# Badge_Schematic.net
KiCad netlist of a schematic drawn in EAGLE
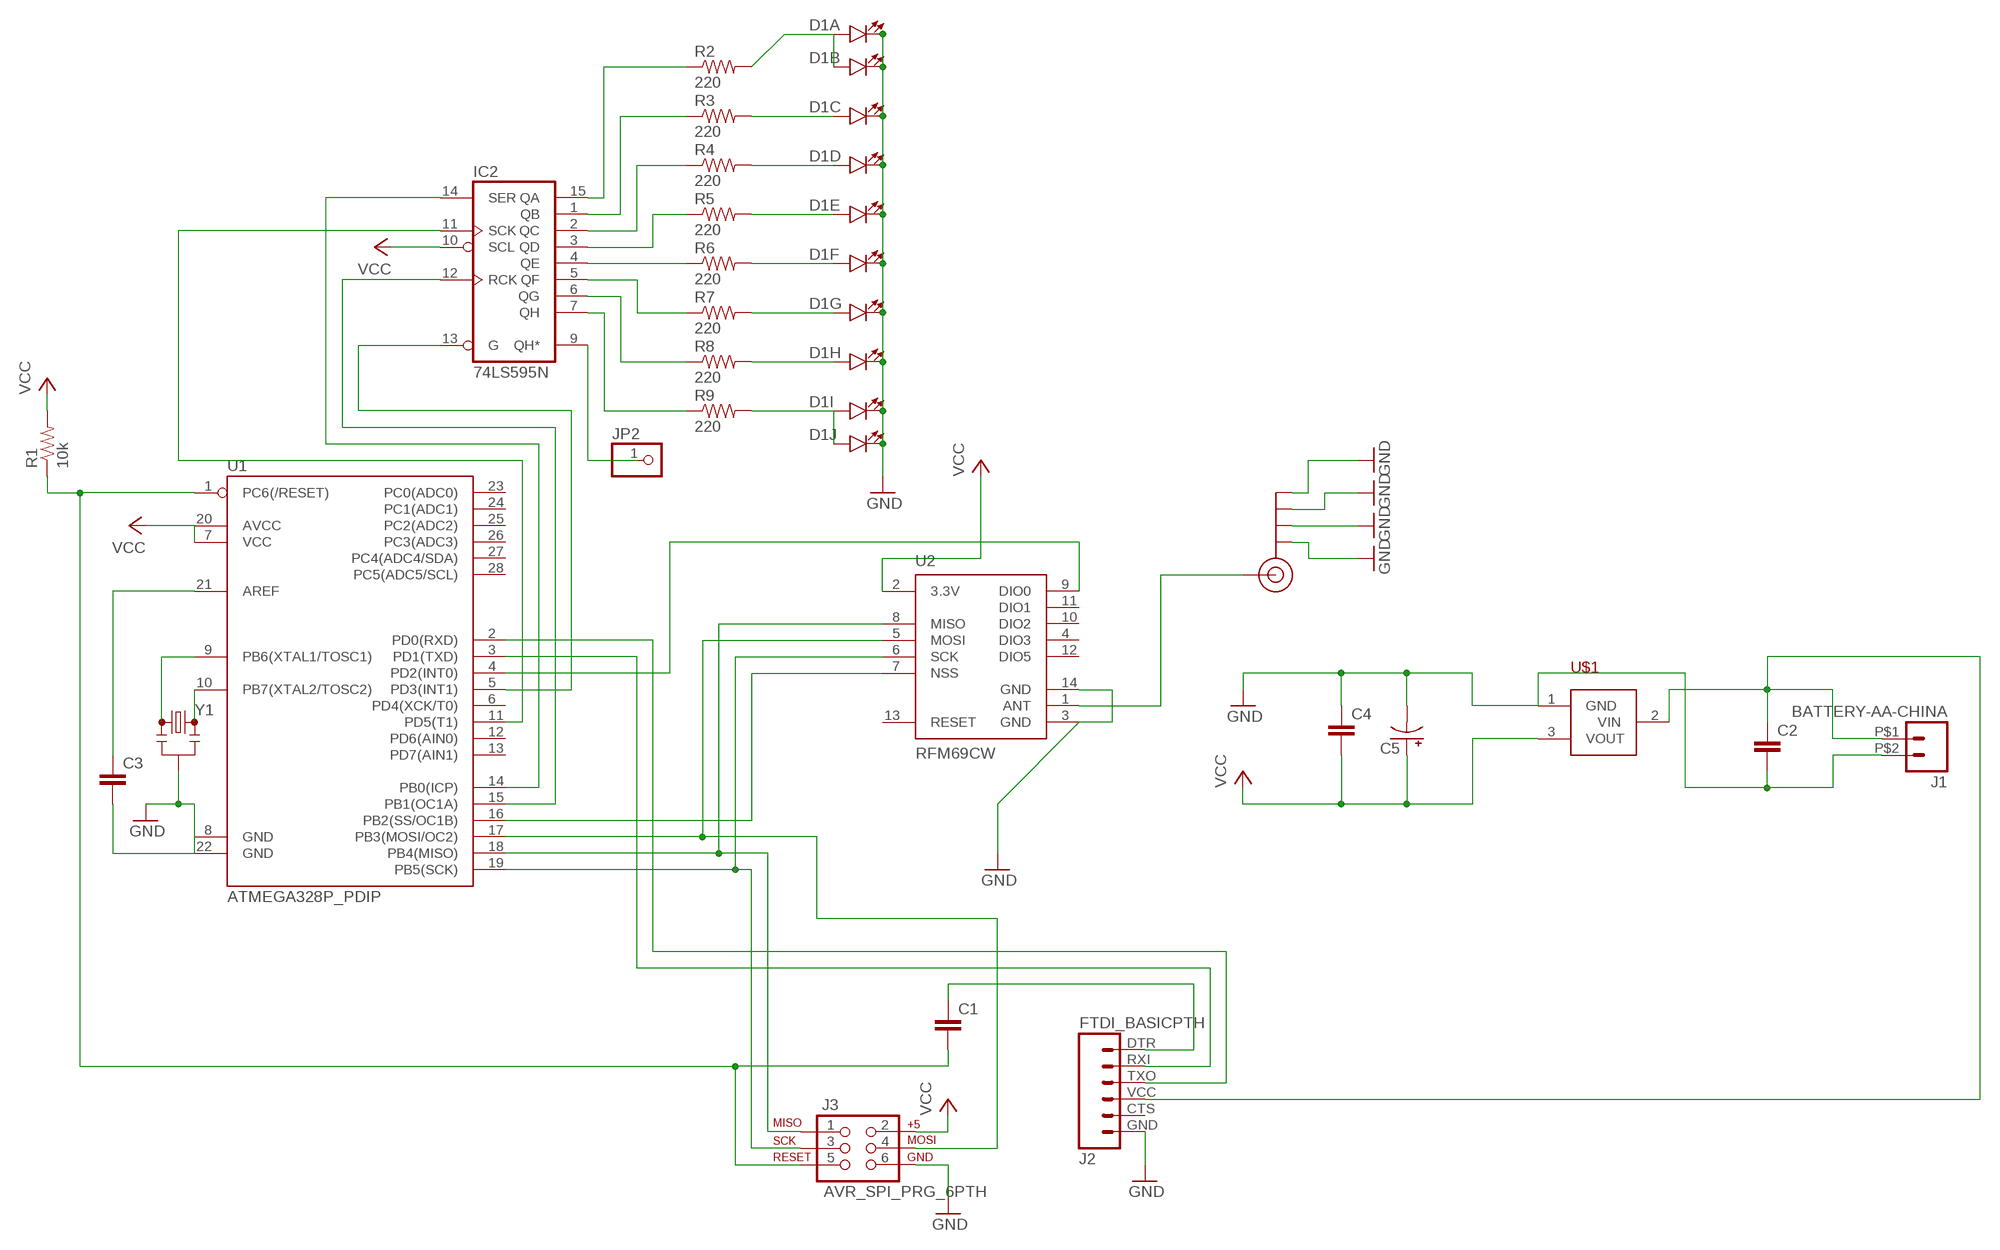
[diagram p0: schematic, sheet 1]

(export (version "E")
  (design (tool "Eeschema 10.0.6"))
  (components
    (comp (ref "C1")
      (value "0.1UF-50V-20%(PTH)KIT-EZ")
      (footprint "eagle-import:CAP-PTH-SMALL-KIT")
      (libsource (lib "eagle-import") (part "0.1UF-50V-20%(PTH)KIT-EZ"))
    )
    (comp (ref "C2")
      (value "0.1UF-50V-20%(PTH)KIT-EZ")
      (footprint "eagle-import:CAP-PTH-SMALL-KIT")
      (libsource (lib "eagle-import") (part "0.1UF-50V-20%(PTH)KIT-EZ"))
    )
    (comp (ref "C3")
      (value "0.1UF-50V-20%(PTH)KIT-EZ")
      (footprint "eagle-import:CAP-PTH-SMALL-KIT")
      (libsource (lib "eagle-import") (part "0.1UF-50V-20%(PTH)KIT-EZ"))
    )
    (comp (ref "C4")
      (value "0.1UF-50V-20%(PTH)KIT-EZ")
      (footprint "eagle-import:CAP-PTH-SMALL-KIT")
      (libsource (lib "eagle-import") (part "0.1UF-50V-20%(PTH)KIT-EZ"))
    )
    (comp (ref "C5")
      (value "10UF-25V-20%(PTH)KIT")
      (footprint "eagle-import:CPOL-RADIAL-10UF-25V-KIT")
      (libsource (lib "eagle-import") (part "10UF-25V-20%(PTH)KIT"))
    )
    (comp (ref "D1")
      (value "LED_BARGRAPH_10")
      (footprint "eagle-import:LED_BARGAPH_10")
      (libsource (lib "eagle-import") (part "LED_BARGRAPH_10"))
    )
    (comp (ref "IC2")
      (value "74LS595N")
      (footprint "eagle-import:DIL16")
      (libsource (lib "eagle-import") (part "74595NLS"))
    )
    (comp (ref "J$1")
      (value "SMA_EDGE")
      (footprint "eagle-import:SMA-EDGE")
      (libsource (lib "eagle-import") (part "SMA_EDGE"))
    )
    (comp (ref "J1")
      (value "BATTERY-AA-CHINA")
      (footprint "eagle-import:BATTERY-AA-CHINA-PACKAGE")
      (libsource (lib "eagle-import") (part "BATTERY-AA-CHINA"))
    )
    (comp (ref "J2")
      (value "FTDI_BASICPTH")
      (footprint "eagle-import:FTDI_BASIC")
      (libsource (lib "eagle-import") (part "FTDI_BASICPTH"))
    )
    (comp (ref "J3")
      (value "AVR_SPI_PRG_6PTH")
      (footprint "eagle-import:2X3")
      (libsource (lib "eagle-import") (part "AVR_SPI_PRG_6PTH"))
    )
    (comp (ref "JP2")
      (value "PINHD-1X1")
      (footprint "eagle-import:1X01")
      (libsource (lib "eagle-import") (part "PINHD-1X1"))
    )
    (comp (ref "R1")
      (value "10k")
      (footprint "eagle-import:AXIAL-0.3")
      (libsource (lib "eagle-import") (part "RESISTORAXIAL-0.3"))
    )
    (comp (ref "R2")
      (value "220")
      (footprint "eagle-import:AXIAL-0.3EZ")
      (libsource (lib "eagle-import") (part "RESISTOREZ"))
    )
    (comp (ref "R3")
      (value "220")
      (footprint "eagle-import:AXIAL-0.3EZ")
      (libsource (lib "eagle-import") (part "RESISTOREZ"))
    )
    (comp (ref "R4")
      (value "220")
      (footprint "eagle-import:AXIAL-0.3EZ")
      (libsource (lib "eagle-import") (part "RESISTOREZ"))
    )
    (comp (ref "R5")
      (value "220")
      (footprint "eagle-import:AXIAL-0.3EZ")
      (libsource (lib "eagle-import") (part "RESISTOREZ"))
    )
    (comp (ref "R6")
      (value "220")
      (footprint "eagle-import:AXIAL-0.3EZ")
      (libsource (lib "eagle-import") (part "RESISTOREZ"))
    )
    (comp (ref "R7")
      (value "220")
      (footprint "eagle-import:AXIAL-0.3EZ")
      (libsource (lib "eagle-import") (part "RESISTOREZ"))
    )
    (comp (ref "R8")
      (value "220")
      (footprint "eagle-import:AXIAL-0.3EZ")
      (libsource (lib "eagle-import") (part "RESISTOREZ"))
    )
    (comp (ref "R9")
      (value "220")
      (footprint "eagle-import:AXIAL-0.3EZ")
      (libsource (lib "eagle-import") (part "RESISTOREZ"))
    )
    (comp (ref "U$1")
      (value "MCP1702-33TO92")
      (footprint "eagle-import:TO-92")
      (libsource (lib "eagle-import") (part "MCP1702-33TO92"))
    )
    (comp (ref "U1")
      (value "ATMEGA328P_PDIP")
      (footprint "eagle-import:DIL28-3")
      (libsource (lib "eagle-import") (part "ATMEGA328P_PDIP"))
    )
    (comp (ref "U2")
      (value "RFM69CW")
      (footprint "eagle-import:RFM69CW-XXXS2")
      (libsource (lib "eagle-import") (part "RFM69CW"))
    )
    (comp (ref "Y1")
      (value "RESONATORPTH")
      (footprint "eagle-import:RESONATOR-PTH")
      (libsource (lib "eagle-import") (part "RESONATORPTH"))
    )
  )
  (nets
    (net (code "1") (name "GND") (class "Default")
      (node (ref "C2") (pin "2") (pinfunction "2_2") (pintype "passive"))
      (node (ref "C3") (pin "2") (pinfunction "2_2") (pintype "passive"))
      (node (ref "C4") (pin "1") (pinfunction "1_1") (pintype "passive"))
      (node (ref "C5") (pin "2") (pinfunction "-_2") (pintype "passive"))
      (node (ref "D1") (pin "11") (pinfunction "C_11") (pintype "passive"))
      (node (ref "D1") (pin "12") (pinfunction "C_12") (pintype "passive"))
      (node (ref "D1") (pin "13") (pinfunction "C_13") (pintype "passive"))
      (node (ref "D1") (pin "14") (pinfunction "C_14") (pintype "passive"))
      (node (ref "D1") (pin "15") (pinfunction "C_15") (pintype "passive"))
      (node (ref "D1") (pin "16") (pinfunction "C_16") (pintype "passive"))
      (node (ref "D1") (pin "17") (pinfunction "C_17") (pintype "passive"))
      (node (ref "D1") (pin "18") (pinfunction "C_18") (pintype "passive"))
      (node (ref "D1") (pin "19") (pinfunction "C_19") (pintype "passive"))
      (node (ref "D1") (pin "20") (pinfunction "C_20") (pintype "passive"))
      (node (ref "J$1") (pin "GND@0") (pinfunction "GND_GND@0") (pintype "bidirectional"))
      (node (ref "J$1") (pin "GND@1") (pinfunction "GND_GND@1") (pintype "bidirectional"))
      (node (ref "J$1") (pin "GND@2") (pinfunction "GND_GND@2") (pintype "bidirectional"))
      (node (ref "J$1") (pin "GND@3") (pinfunction "GND_GND@3") (pintype "bidirectional"))
      (node (ref "J1") (pin "P$2") (pinfunction "2_P$2") (pintype "passive"))
      (node (ref "J2") (pin "GND") (pinfunction "6_GND") (pintype "passive"))
      (node (ref "J3") (pin "6") (pinfunction "6_6") (pintype "passive"))
      (node (ref "U$1") (pin "1") (pinfunction "GND_1") (pintype "power_in"))
      (node (ref "U1") (pin "22") (pinfunction "GND_22") (pintype "bidirectional"))
      (node (ref "U1") (pin "8") (pinfunction "GND_8") (pintype "bidirectional"))
      (node (ref "U2") (pin "14") (pinfunction "GND_14") (pintype "power_in"))
      (node (ref "U2") (pin "3") (pinfunction "GND_3") (pintype "power_in"))
      (node (ref "Y1") (pin "2") (pinfunction "2_2") (pintype "passive"))
    )
    (net (code "2") (name "Net-(D1A-A)") (class "Default")
      (node (ref "D1") (pin "1") (pinfunction "A_1") (pintype "passive"))
      (node (ref "D1") (pin "2") (pinfunction "A_2") (pintype "passive"))
      (node (ref "R2") (pin "P$2") (pinfunction "2_P$2") (pintype "passive"))
    )
    (net (code "3") (name "Net-(D1C-A)") (class "Default")
      (node (ref "D1") (pin "3") (pinfunction "A_3") (pintype "passive"))
      (node (ref "R3") (pin "P$2") (pinfunction "2_P$2") (pintype "passive"))
    )
    (net (code "4") (name "Net-(D1D-A)") (class "Default")
      (node (ref "D1") (pin "4") (pinfunction "A_4") (pintype "passive"))
      (node (ref "R4") (pin "P$2") (pinfunction "2_P$2") (pintype "passive"))
    )
    (net (code "5") (name "Net-(D1E-A)") (class "Default")
      (node (ref "D1") (pin "5") (pinfunction "A_5") (pintype "passive"))
      (node (ref "R5") (pin "P$2") (pinfunction "2_P$2") (pintype "passive"))
    )
    (net (code "6") (name "Net-(D1F-A)") (class "Default")
      (node (ref "D1") (pin "6") (pinfunction "A_6") (pintype "passive"))
      (node (ref "R6") (pin "P$2") (pinfunction "2_P$2") (pintype "passive"))
    )
    (net (code "7") (name "Net-(D1G-A)") (class "Default")
      (node (ref "D1") (pin "7") (pinfunction "A_7") (pintype "passive"))
      (node (ref "R7") (pin "P$2") (pinfunction "2_P$2") (pintype "passive"))
    )
    (net (code "8") (name "Net-(D1H-A)") (class "Default")
      (node (ref "D1") (pin "8") (pinfunction "A_8") (pintype "passive"))
      (node (ref "R8") (pin "P$2") (pinfunction "2_P$2") (pintype "passive"))
    )
    (net (code "9") (name "Net-(D1I-A)") (class "Default")
      (node (ref "D1") (pin "10") (pinfunction "A_10") (pintype "passive"))
      (node (ref "D1") (pin "9") (pinfunction "A_9") (pintype "passive"))
      (node (ref "R9") (pin "P$2") (pinfunction "2_P$2") (pintype "passive"))
    )
    (net (code "10") (name "Net-(IC2A-G)") (class "Default")
      (node (ref "IC2") (pin "13") (pinfunction "G_13") (pintype "input"))
      (node (ref "U1") (pin "5") (pinfunction "PD3(INT1)_5") (pintype "bidirectional"))
    )
    (net (code "11") (name "Net-(IC2A-QA)") (class "Default")
      (node (ref "IC2") (pin "15") (pinfunction "QA_15") (pintype "tri_state"))
      (node (ref "R2") (pin "P$1") (pinfunction "1_P$1") (pintype "passive"))
    )
    (net (code "12") (name "Net-(IC2A-QB)") (class "Default")
      (node (ref "IC2") (pin "1") (pinfunction "QB_1") (pintype "tri_state"))
      (node (ref "R3") (pin "P$1") (pinfunction "1_P$1") (pintype "passive"))
    )
    (net (code "13") (name "Net-(IC2A-QC)") (class "Default")
      (node (ref "IC2") (pin "2") (pinfunction "QC_2") (pintype "tri_state"))
      (node (ref "R4") (pin "P$1") (pinfunction "1_P$1") (pintype "passive"))
    )
    (net (code "14") (name "Net-(IC2A-QD)") (class "Default")
      (node (ref "IC2") (pin "3") (pinfunction "QD_3") (pintype "tri_state"))
      (node (ref "R5") (pin "P$1") (pinfunction "1_P$1") (pintype "passive"))
    )
    (net (code "15") (name "Net-(IC2A-QE)") (class "Default")
      (node (ref "IC2") (pin "4") (pinfunction "QE_4") (pintype "tri_state"))
      (node (ref "R6") (pin "P$1") (pinfunction "1_P$1") (pintype "passive"))
    )
    (net (code "16") (name "Net-(IC2A-QF)") (class "Default")
      (node (ref "IC2") (pin "5") (pinfunction "QF_5") (pintype "tri_state"))
      (node (ref "R7") (pin "P$1") (pinfunction "1_P$1") (pintype "passive"))
    )
    (net (code "17") (name "Net-(IC2A-QG)") (class "Default")
      (node (ref "IC2") (pin "6") (pinfunction "QG_6") (pintype "tri_state"))
      (node (ref "R8") (pin "P$1") (pinfunction "1_P$1") (pintype "passive"))
    )
    (net (code "18") (name "Net-(IC2A-QH)") (class "Default")
      (node (ref "IC2") (pin "7") (pinfunction "QH_7") (pintype "tri_state"))
      (node (ref "R9") (pin "P$1") (pinfunction "1_P$1") (pintype "passive"))
    )
    (net (code "19") (name "Net-(IC2A-QH*)") (class "Default")
      (node (ref "IC2") (pin "9") (pinfunction "QH*_9") (pintype "tri_state"))
      (node (ref "JP2") (pin "1") (pinfunction "1_1") (pintype "passive"))
    )
    (net (code "20") (name "Net-(IC2A-RCK)") (class "Default")
      (node (ref "IC2") (pin "12") (pinfunction "RCK_12") (pintype "input"))
      (node (ref "U1") (pin "15") (pinfunction "PB1(OC1A)_15") (pintype "bidirectional"))
    )
    (net (code "21") (name "Net-(IC2A-SCK)") (class "Default")
      (node (ref "IC2") (pin "11") (pinfunction "SCK_11") (pintype "input"))
      (node (ref "U1") (pin "11") (pinfunction "PD5(T1)_11") (pintype "bidirectional"))
    )
    (net (code "22") (name "Net-(IC2A-SER)") (class "Default")
      (node (ref "IC2") (pin "14") (pinfunction "SER_14") (pintype "input"))
      (node (ref "U1") (pin "14") (pinfunction "PB0(ICP)_14") (pintype "bidirectional"))
    )
    (net (code "23") (name "Net-(J$1-SIGNAL)") (class "Default")
      (node (ref "J$1") (pin "SIG") (pinfunction "SIGNAL_SIG") (pintype "bidirectional"))
      (node (ref "U2") (pin "1") (pinfunction "ANT_1") (pintype "passive"))
    )
    (net (code "24") (name "Net-(J1-1)") (class "Default")
      (node (ref "C2") (pin "1") (pinfunction "1_1") (pintype "passive"))
      (node (ref "J1") (pin "P$1") (pinfunction "1_P$1") (pintype "passive"))
      (node (ref "J2") (pin "VCC") (pinfunction "4_VCC") (pintype "passive"))
      (node (ref "U$1") (pin "2") (pinfunction "VIN_2") (pintype "input"))
    )
    (net (code "25") (name "Net-(J2-1)") (class "Default")
      (node (ref "C1") (pin "1") (pinfunction "1_1") (pintype "passive"))
      (node (ref "J2") (pin "DTR") (pinfunction "1_DTR") (pintype "passive"))
    )
    (net (code "26") (name "Net-(J2-2)") (class "Default")
      (node (ref "J2") (pin "RXI") (pinfunction "2_RXI") (pintype "passive"))
      (node (ref "U1") (pin "3") (pinfunction "PD1(TXD)_3") (pintype "bidirectional"))
    )
    (net (code "27") (name "Net-(J2-3)") (class "Default")
      (node (ref "J2") (pin "TXO") (pinfunction "3_TXO") (pintype "passive"))
      (node (ref "U1") (pin "2") (pinfunction "PD0(RXD)_2") (pintype "bidirectional"))
    )
    (net (code "28") (name "Net-(R1-1)") (class "Default")
      (node (ref "C1") (pin "2") (pinfunction "2_2") (pintype "passive"))
      (node (ref "J3") (pin "5") (pinfunction "5_5") (pintype "passive"))
      (node (ref "R1") (pin "P$1") (pinfunction "1_P$1") (pintype "passive"))
      (node (ref "U1") (pin "1") (pinfunction "PC6(/RESET)_1") (pintype "bidirectional"))
    )
    (net (code "29") (name "Net-(U1-AREF)") (class "Default")
      (node (ref "C3") (pin "1") (pinfunction "1_1") (pintype "passive"))
      (node (ref "U1") (pin "21") (pinfunction "AREF_21") (pintype "bidirectional"))
    )
    (net (code "30") (name "Net-(U1-PB2(SS{slash}OC1B))") (class "Default")
      (node (ref "U1") (pin "16") (pinfunction "PB2(SS/OC1B)_16") (pintype "bidirectional"))
      (node (ref "U2") (pin "7") (pinfunction "NSS_7") (pintype "input"))
    )
    (net (code "31") (name "Net-(U1-PB3(MOSI{slash}OC2))") (class "Default")
      (node (ref "J3") (pin "4") (pinfunction "4_4") (pintype "passive"))
      (node (ref "U1") (pin "17") (pinfunction "PB3(MOSI/OC2)_17") (pintype "bidirectional"))
      (node (ref "U2") (pin "5") (pinfunction "MOSI_5") (pintype "input"))
    )
    (net (code "32") (name "Net-(U1-PB4(MISO))") (class "Default")
      (node (ref "J3") (pin "1") (pinfunction "1_1") (pintype "passive"))
      (node (ref "U1") (pin "18") (pinfunction "PB4(MISO)_18") (pintype "bidirectional"))
      (node (ref "U2") (pin "8") (pinfunction "MISO_8") (pintype "bidirectional"))
    )
    (net (code "33") (name "Net-(U1-PB5(SCK))") (class "Default")
      (node (ref "J3") (pin "3") (pinfunction "3_3") (pintype "passive"))
      (node (ref "U1") (pin "19") (pinfunction "PB5(SCK)_19") (pintype "bidirectional"))
      (node (ref "U2") (pin "6") (pinfunction "SCK_6") (pintype "input"))
    )
    (net (code "34") (name "Net-(U1-PB6(XTAL1{slash}TOSC1))") (class "Default")
      (node (ref "U1") (pin "9") (pinfunction "PB6(XTAL1/TOSC1)_9") (pintype "bidirectional"))
      (node (ref "Y1") (pin "1") (pinfunction "1_1") (pintype "passive"))
    )
    (net (code "35") (name "Net-(U1-PB7(XTAL2{slash}TOSC2))") (class "Default")
      (node (ref "U1") (pin "10") (pinfunction "PB7(XTAL2/TOSC2)_10") (pintype "bidirectional"))
      (node (ref "Y1") (pin "3") (pinfunction "3_3") (pintype "passive"))
    )
    (net (code "36") (name "Net-(U1-PD2(INT0))") (class "Default")
      (node (ref "U1") (pin "4") (pinfunction "PD2(INT0)_4") (pintype "bidirectional"))
      (node (ref "U2") (pin "9") (pinfunction "DIO0_9") (pintype "bidirectional"))
    )
    (net (code "37") (name "VCC") (class "Default")
      (node (ref "C4") (pin "2") (pinfunction "2_2") (pintype "passive"))
      (node (ref "C5") (pin "1") (pinfunction "+_1") (pintype "passive"))
      (node (ref "IC2") (pin "10") (pinfunction "SCL_10") (pintype "input"))
      (node (ref "J3") (pin "2") (pinfunction "2_2") (pintype "passive"))
      (node (ref "R1") (pin "P$2") (pinfunction "2_P$2") (pintype "passive"))
      (node (ref "U$1") (pin "3") (pinfunction "VOUT_3") (pintype "output"))
      (node (ref "U1") (pin "20") (pinfunction "AVCC_20") (pintype "bidirectional"))
      (node (ref "U1") (pin "7") (pinfunction "VCC_7") (pintype "bidirectional"))
      (node (ref "U2") (pin "2") (pinfunction "3.3V_2") (pintype "power_in"))
    )
    (net (code "38") (name "unconnected-(J2-5-PadCTS)") (class "Default")
      (node (ref "J2") (pin "CTS") (pinfunction "5_CTS") (pintype "passive"))
    )
    (net (code "39") (name "unconnected-(U1-PC0(ADC0)-Pad23)") (class "Default")
      (node (ref "U1") (pin "23") (pinfunction "PC0(ADC0)_23") (pintype "bidirectional"))
    )
    (net (code "40") (name "unconnected-(U1-PC1(ADC1)-Pad24)") (class "Default")
      (node (ref "U1") (pin "24") (pinfunction "PC1(ADC1)_24") (pintype "bidirectional"))
    )
    (net (code "41") (name "unconnected-(U1-PC2(ADC2)-Pad25)") (class "Default")
      (node (ref "U1") (pin "25") (pinfunction "PC2(ADC2)_25") (pintype "bidirectional"))
    )
    (net (code "42") (name "unconnected-(U1-PC3(ADC3)-Pad26)") (class "Default")
      (node (ref "U1") (pin "26") (pinfunction "PC3(ADC3)_26") (pintype "bidirectional"))
    )
    (net (code "43") (name "unconnected-(U1-PC4(ADC4{slash}SDA)-Pad27)") (class "Default")
      (node (ref "U1") (pin "27") (pinfunction "PC4(ADC4/SDA)_27") (pintype "bidirectional"))
    )
    (net (code "44") (name "unconnected-(U1-PC5(ADC5{slash}SCL)-Pad28)") (class "Default")
      (node (ref "U1") (pin "28") (pinfunction "PC5(ADC5/SCL)_28") (pintype "bidirectional"))
    )
    (net (code "45") (name "unconnected-(U1-PD4(XCK{slash}T0)-Pad6)") (class "Default")
      (node (ref "U1") (pin "6") (pinfunction "PD4(XCK/T0)_6") (pintype "bidirectional"))
    )
    (net (code "46") (name "unconnected-(U1-PD6(AIN0)-Pad12)") (class "Default")
      (node (ref "U1") (pin "12") (pinfunction "PD6(AIN0)_12") (pintype "bidirectional"))
    )
    (net (code "47") (name "unconnected-(U1-PD7(AIN1)-Pad13)") (class "Default")
      (node (ref "U1") (pin "13") (pinfunction "PD7(AIN1)_13") (pintype "bidirectional"))
    )
    (net (code "48") (name "unconnected-(U2-DIO1-Pad11)") (class "Default")
      (node (ref "U2") (pin "11") (pinfunction "DIO1_11") (pintype "bidirectional"))
    )
    (net (code "49") (name "unconnected-(U2-DIO2-Pad10)") (class "Default")
      (node (ref "U2") (pin "10") (pinfunction "DIO2_10") (pintype "bidirectional"))
    )
    (net (code "50") (name "unconnected-(U2-DIO3-Pad4)") (class "Default")
      (node (ref "U2") (pin "4") (pinfunction "DIO3_4") (pintype "bidirectional"))
    )
    (net (code "51") (name "unconnected-(U2-DIO5-Pad12)") (class "Default")
      (node (ref "U2") (pin "12") (pinfunction "DIO5_12") (pintype "bidirectional"))
    )
    (net (code "52") (name "unconnected-(U2-RESET-Pad13)") (class "Default")
      (node (ref "U2") (pin "13") (pinfunction "RESET_13") (pintype "input"))
    )
  )
)
